# Gate_Strobe.net
KiCad netlist of a schematic drawn in Altium Designer
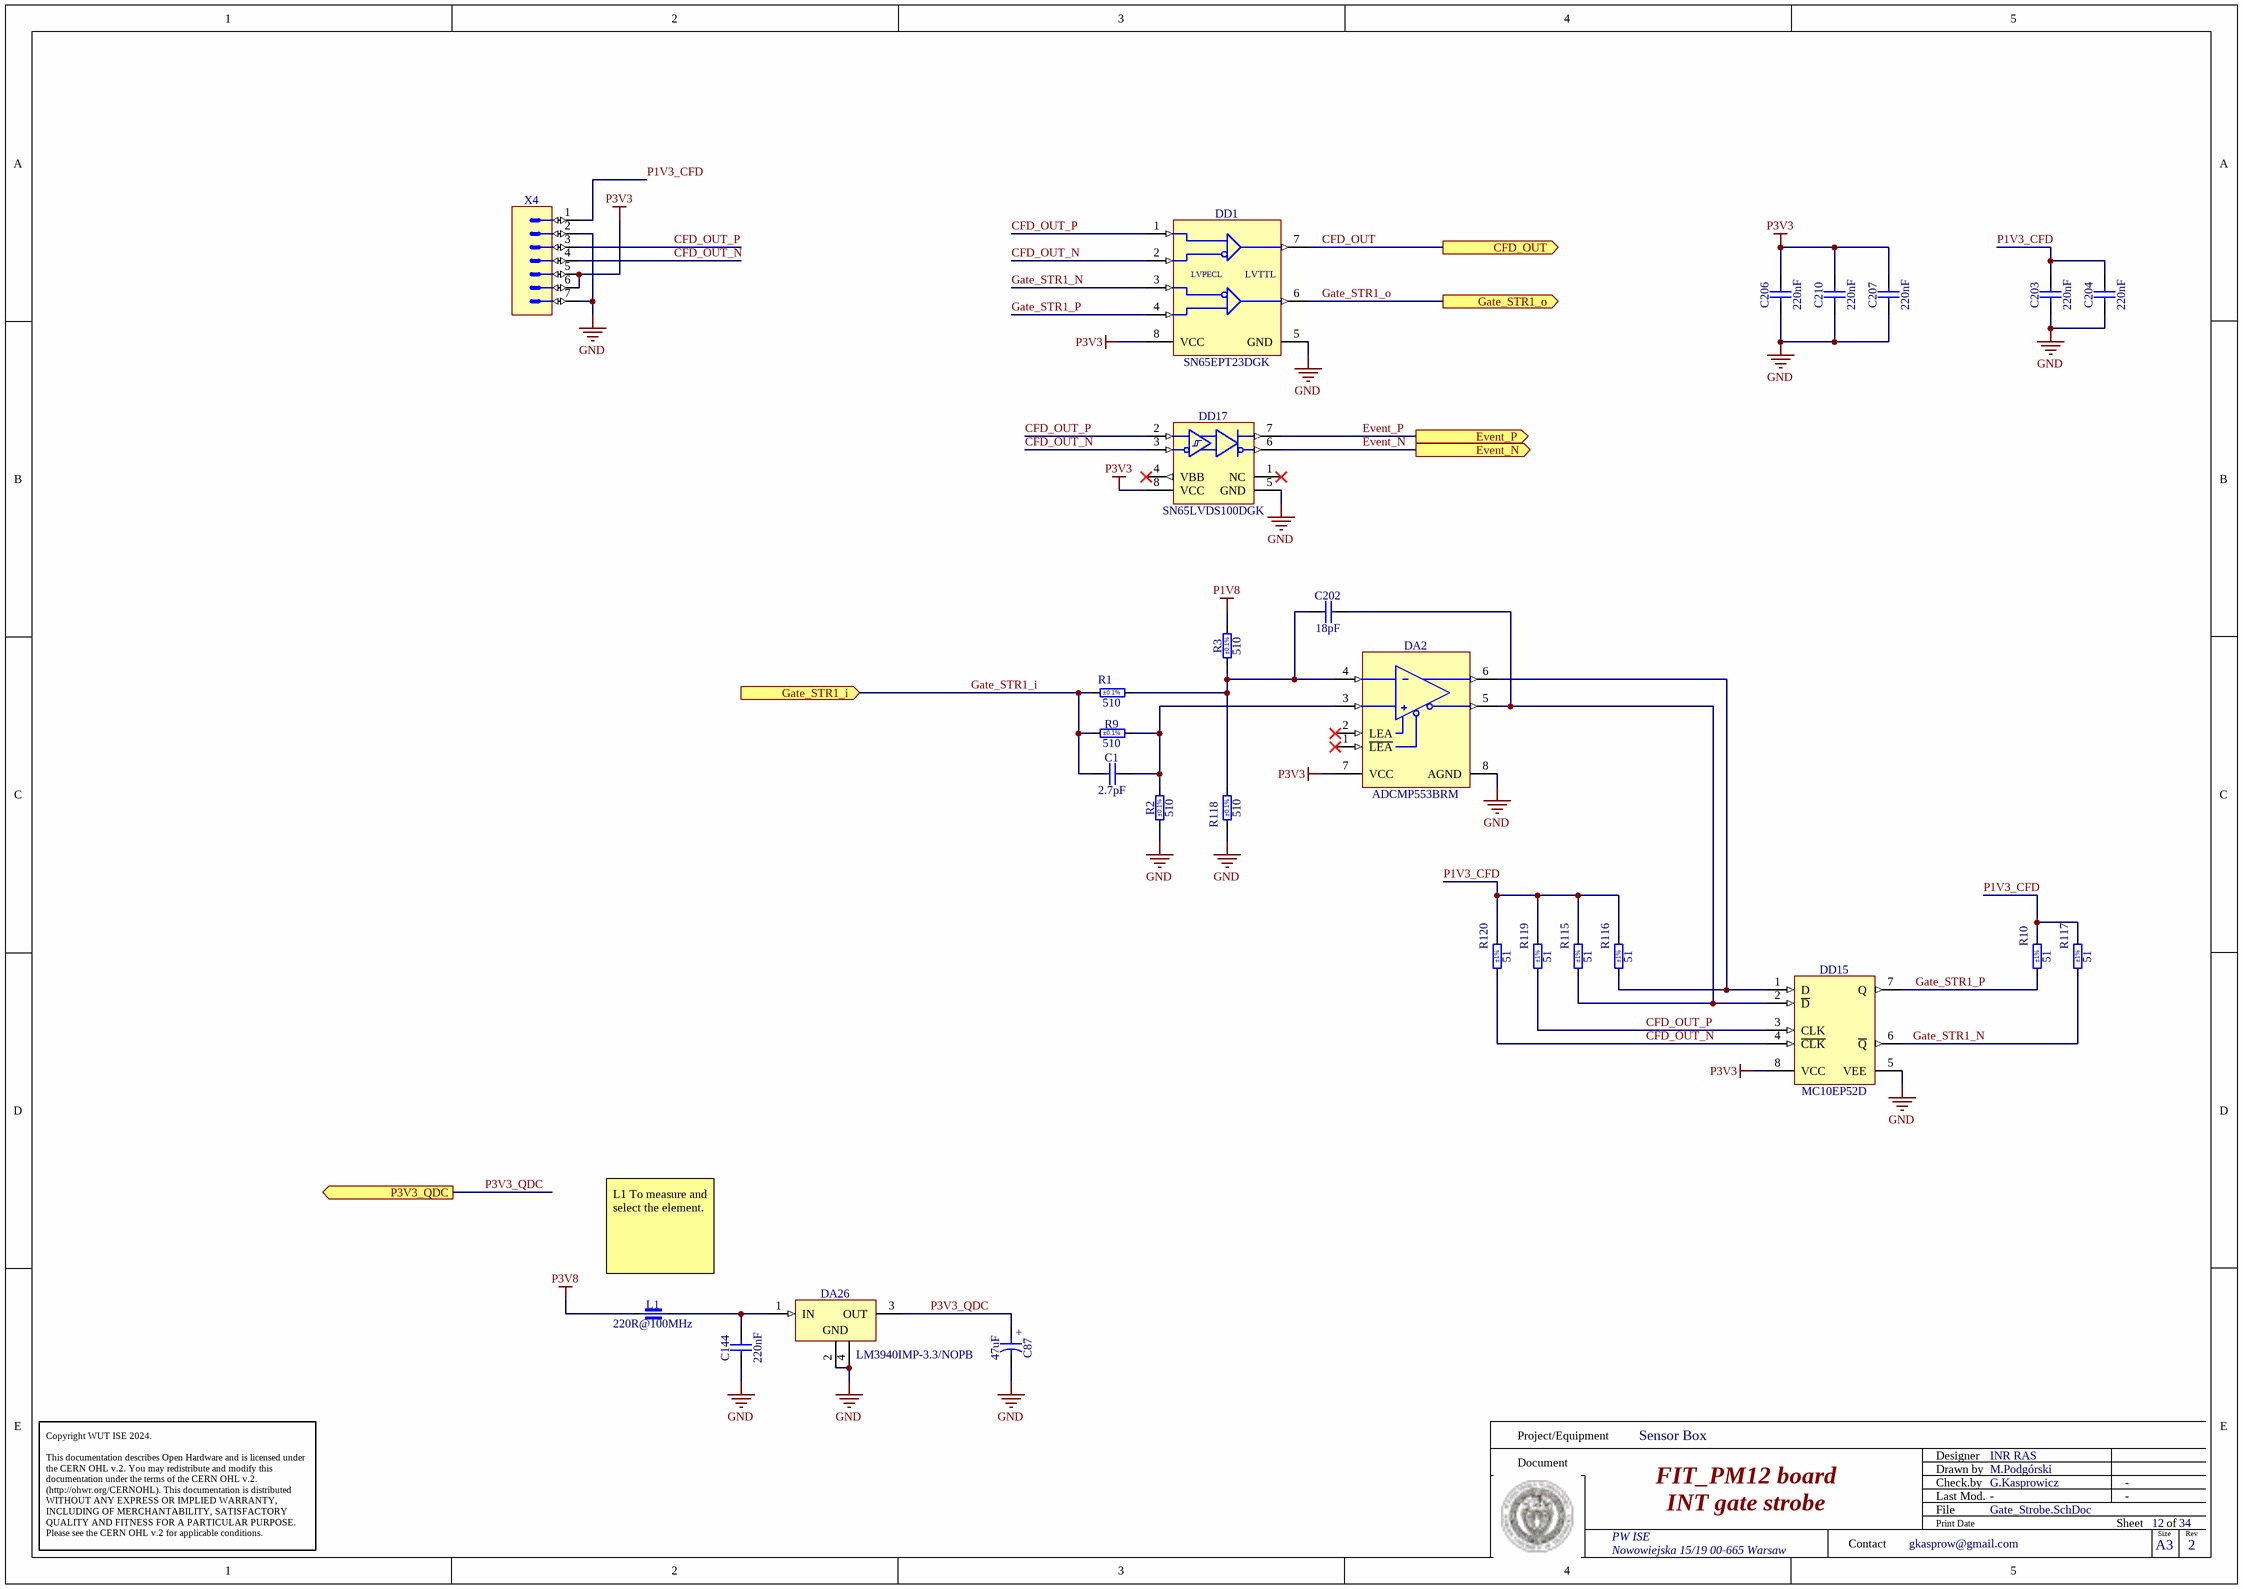
[diagram p0: Gate_Strobe.SchDoc]

(export (version "E")
  (design (tool "Eeschema 10.0.6"))
  (components
    (comp (ref "C1")
      (value "2.7pF")
      (footprint "CAPC2012X135N")
      (description "Non-polarised capacitor")
      (fields
        (field (name "PART NUMBER") "CC0805_2.7PF_250V_0.05PF_NP0")
        (field (name "VOLTAGE") "50V")
        (field (name "AUTHOR") "CERN DEM HF")
      )
      (libsource (lib "Capacitors") (part "Capacitor - non polarized"))
    )
    (comp (ref "C87")
      (value "47uF")
      (footprint "CAPAE530X610N")
      (description "Polarised capacitor")
      (fields
        (field (name "PART NUMBER") "CAE530-610_47UF_16V_20%")
        (field (name "VOLTAGE") "16V")
        (field (name "AUTHOR") "CERN DEM HF")
      )
      (libsource (lib "Capacitors") (part "Capacitor - polarized"))
    )
    (comp (ref "C144")
      (value "220nF")
      (footprint "CAPC2012X135N")
      (description "Non-polarised capacitor")
      (fields
        (field (name "PART NUMBER") "CC0805_220NF_50V_10%_X7R")
        (field (name "VOLTAGE") "50V")
        (field (name "AUTHOR") "CERN DEM JLC")
      )
      (libsource (lib "Capacitors") (part "Capacitor - non polarized"))
    )
    (comp (ref "C202")
      (value "18pF")
      (footprint "CAPC2012X88N")
      (description "Non-polarised capacitor")
      (fields
        (field (name "PART NUMBER") "CC0805_18PF_50V_1%_C0G")
        (field (name "VOLTAGE") "50V")
        (field (name "AUTHOR") "CERN DEM JLC")
      )
      (libsource (lib "Capacitors") (part "Capacitor - non polarized"))
    )
    (comp (ref "C203")
      (value "220nF")
      (footprint "CAPC2012X135N")
      (description "Non-polarised capacitor")
      (fields
        (field (name "PART NUMBER") "CC0805_220NF_50V_10%_X7R")
        (field (name "VOLTAGE") "50V")
        (field (name "AUTHOR") "CERN DEM JLC")
      )
      (libsource (lib "Capacitors") (part "Capacitor - non polarized"))
    )
    (comp (ref "C204")
      (value "220nF")
      (footprint "CAPC2012X135N")
      (description "Non-polarised capacitor")
      (fields
        (field (name "PART NUMBER") "CC0805_220NF_50V_10%_X7R")
        (field (name "VOLTAGE") "50V")
        (field (name "AUTHOR") "CERN DEM JLC")
      )
      (libsource (lib "Capacitors") (part "Capacitor - non polarized"))
    )
    (comp (ref "C206")
      (value "220nF")
      (footprint "CAPC2012X135N")
      (description "Non-polarised capacitor")
      (fields
        (field (name "PART NUMBER") "CC0805_220NF_50V_10%_X7R")
        (field (name "VOLTAGE") "50V")
        (field (name "AUTHOR") "CERN DEM JLC")
      )
      (libsource (lib "Capacitors") (part "Capacitor - non polarized"))
    )
    (comp (ref "C207")
      (value "220nF")
      (footprint "CAPC2012X135N")
      (description "Non-polarised capacitor")
      (fields
        (field (name "PART NUMBER") "CC0805_220NF_50V_10%_X7R")
        (field (name "VOLTAGE") "50V")
        (field (name "AUTHOR") "CERN DEM JLC")
      )
      (libsource (lib "Capacitors") (part "Capacitor - non polarized"))
    )
    (comp (ref "C210")
      (value "220nF")
      (footprint "CAPC2012X135N")
      (description "Non-polarised capacitor")
      (fields
        (field (name "PART NUMBER") "CC0805_220NF_50V_10%_X7R")
        (field (name "VOLTAGE") "50V")
        (field (name "AUTHOR") "CERN DEM JLC")
      )
      (libsource (lib "Capacitors") (part "Capacitor - non polarized"))
    )
    (comp (ref "DA2")
      (value "ADCMP553BRM")
      (footprint "SOP65P490X110-8N")
      (description "Single-Supply, High Speed PECL/LVPECL Comparators")
      (fields (field (name "MANUFACTURER") "ANALOG DEVICES") (field (name "AUTHOR") "CERN DEM HF"))
      (libsource (lib "ICs And Semiconductors") (part "ADCMP553BRM"))
    )
    (comp (ref "DA26")
      (value "LM3940IMP-3.3/NOPB")
      (footprint "SOT230P700X180-4N")
      (description "3-Terminal Regulator 1=IN 2=GND 3=OUT 4=GND")
      (fields
        (field (name "MANUFACTURER") "TEXAS INSTRUMENTS")
        (field (name "MANUFACTURER PART NUMBER") "LM3940IMP-3.3")
        (field (name "AUTHOR") "CERN DEM JLC")
      )
      (libsource (lib "ICs And Semiconductors") (part "REG3+1 1IN-2GND-3OUT+4GND"))
    )
    (comp (ref "DD1")
      (value "SN65EPT23DGK")
      (footprint "SOP65P490X110-8N")
      (description "5V PECL to TTL Translator")
      (fields (field (name "MANUFACTURER") "TEXAS INSTRUMENTS") (field (name "AUTHOR") "CERN DEM HF"))
      (libsource (lib "ICs And Semiconductors") (part "SN65EPT23"))
    )
    (comp (ref "DD15")
      (value "MC10EP52D")
      (footprint "SOIC127P600X175-8N")
      (description "3.3V/5V ECL Differential Data and Clock D Flip-Flop")
      (fields (field (name "MANUFACTURER") "ON SEMICONDUCTOR") (field (name "AUTHOR") "CERN DEM HF"))
      (libsource (lib "ICs And Semiconductors") (part "100EP52"))
    )
    (comp (ref "DD17")
      (value "SN65LVDS100DGK")
      (footprint "SOP65P490X110-8N")
      (description "Differential LVDS Translator/Repeater")
      (fields (field (name "MANUFACTURER") "TEXAS INSTRUMENTS") (field (name "AUTHOR") "CERN DEM JLC"))
      (libsource (lib "ICs And Semiconductors") (part "SN65LVDS100"))
    )
    (comp (ref "L1")
      (value "220R@100MHz")
      (footprint "INDC2012X105N")
      (fields
        (field (name "PART NUMBER") "IND0805_TDK_MPZ2012S221A")
        (field (name "POWER") "3A")
        (field (name "TOLERANCE") "±25%")
        (field (name "AUTHOR") "CERN DEM HF")
      )
      (libsource (lib "Inductors & Transformers") (part "Ferrite Bead"))
    )
    (comp (ref "R1")
      (value "510")
      (footprint "RESC2012X60N")
      (description "Resistor - 0.1%")
      (fields
        (field (name "TOLERANCE") "±0.1%")
        (field (name "PART NUMBER") "R0805_510R_0.1%_0.125W_10PPM")
        (field (name "POWER") "0.125W")
        (field (name "AUTHOR") "CERN DEM HF")
      )
      (libsource (lib "Resistors") (part "Resistor - 0.1%"))
    )
    (comp (ref "R2")
      (value "510")
      (footprint "RESC2012X60N")
      (description "Resistor - 0.1%")
      (fields
        (field (name "TOLERANCE") "±0.1%")
        (field (name "PART NUMBER") "R0805_510R_0.1%_0.125W_10PPM")
        (field (name "POWER") "0.125W")
        (field (name "AUTHOR") "CERN DEM HF")
      )
      (libsource (lib "Resistors") (part "Resistor - 0.1%"))
    )
    (comp (ref "R3")
      (value "510")
      (footprint "RESC2012X60N")
      (description "Resistor - 0.1%")
      (fields
        (field (name "TOLERANCE") "±0.1%")
        (field (name "PART NUMBER") "R0805_510R_0.1%_0.125W_10PPM")
        (field (name "POWER") "0.125W")
        (field (name "AUTHOR") "CERN DEM HF")
      )
      (libsource (lib "Resistors") (part "Resistor - 0.1%"))
    )
    (comp (ref "R9")
      (value "510")
      (footprint "RESC2012X60N")
      (description "Resistor - 0.1%")
      (fields
        (field (name "TOLERANCE") "±0.1%")
        (field (name "PART NUMBER") "R0805_510R_0.1%_0.125W_10PPM")
        (field (name "POWER") "0.125W")
        (field (name "AUTHOR") "CERN DEM HF")
      )
      (libsource (lib "Resistors") (part "Resistor - 0.1%"))
    )
    (comp (ref "R10")
      (value "51")
      (footprint "RESC2012X60N")
      (description "Resistor - 1%")
      (fields
        (field (name "TOLERANCE") "±1%")
        (field (name "PART NUMBER") "R0805_51R_1%_0.125W_100PPM")
        (field (name "POWER") "0.125W")
        (field (name "AUTHOR") "CERN DEM JLC")
      )
      (libsource (lib "Resistors") (part "Resistor - 1%"))
    )
    (comp (ref "R115")
      (value "51")
      (footprint "RESC2012X60N")
      (description "Resistor - 1%")
      (fields
        (field (name "TOLERANCE") "±1%")
        (field (name "PART NUMBER") "R0805_51R_1%_0.125W_100PPM")
        (field (name "POWER") "0.125W")
        (field (name "AUTHOR") "CERN DEM JLC")
      )
      (libsource (lib "Resistors") (part "Resistor - 1%"))
    )
    (comp (ref "R116")
      (value "51")
      (footprint "RESC2012X60N")
      (description "Resistor - 1%")
      (fields
        (field (name "TOLERANCE") "±1%")
        (field (name "PART NUMBER") "R0805_51R_1%_0.125W_100PPM")
        (field (name "POWER") "0.125W")
        (field (name "AUTHOR") "CERN DEM JLC")
      )
      (libsource (lib "Resistors") (part "Resistor - 1%"))
    )
    (comp (ref "R117")
      (value "51")
      (footprint "RESC2012X60N")
      (description "Resistor - 1%")
      (fields
        (field (name "TOLERANCE") "±1%")
        (field (name "PART NUMBER") "R0805_51R_1%_0.125W_100PPM")
        (field (name "POWER") "0.125W")
        (field (name "AUTHOR") "CERN DEM JLC")
      )
      (libsource (lib "Resistors") (part "Resistor - 1%"))
    )
    (comp (ref "R118")
      (value "510")
      (footprint "RESC2012X60N")
      (description "Resistor - 0.1%")
      (fields
        (field (name "TOLERANCE") "±0.1%")
        (field (name "PART NUMBER") "R0805_510R_0.1%_0.125W_10PPM")
        (field (name "POWER") "0.125W")
        (field (name "AUTHOR") "CERN DEM HF")
      )
      (libsource (lib "Resistors") (part "Resistor - 0.1%"))
    )
    (comp (ref "R119")
      (value "51")
      (footprint "RESC2012X60N")
      (description "Resistor - 1%")
      (fields
        (field (name "TOLERANCE") "±1%")
        (field (name "PART NUMBER") "R0805_51R_1%_0.125W_100PPM")
        (field (name "POWER") "0.125W")
        (field (name "AUTHOR") "CERN DEM JLC")
      )
      (libsource (lib "Resistors") (part "Resistor - 1%"))
    )
    (comp (ref "R120")
      (value "51")
      (footprint "RESC2012X60N")
      (description "Resistor - 1%")
      (fields
        (field (name "TOLERANCE") "±1%")
        (field (name "PART NUMBER") "R0805_51R_1%_0.125W_100PPM")
        (field (name "POWER") "0.125W")
        (field (name "AUTHOR") "CERN DEM JLC")
      )
      (libsource (lib "Resistors") (part "Resistor - 1%"))
    )
    (comp (ref "X4")
      (value "Header 7")
      (footprint "SAMTEC_DW-07-09-L-S-470")
      (description "Connector 7 Male")
      (fields
        (field (name "PART NUMBER") "SAMTEC_DW-07-09-L-S-470")
        (field (name "MANUFACTURER") "SAMTEC")
        (field (name "AUTHOR") "CERN DEM HF")
      )
      (libsource (lib "Connectors") (part "Connector 7 Male"))
    )
  )
  (nets
    (net (code "1") (name "/CFD_OUT") (class "Default")
      (node (ref "DD1") (pin "7") (pinfunction "Q0_7") (pintype "output"))
    )
    (net (code "2") (name "/CFD_OUT_N") (class "Default")
      (node (ref "DD1") (pin "2") (pinfunction "~{D0}_2") (pintype "input"))
      (node (ref "DD15") (pin "4") (pinfunction "~{CLK}_4") (pintype "input"))
      (node (ref "DD17") (pin "3") (pinfunction "B_3") (pintype "input"))
      (node (ref "R120") (pin "1") (pinfunction "1_1") (pintype "passive"))
      (node (ref "X4") (pin "4") (pinfunction "4_4") (pintype "bidirectional"))
    )
    (net (code "3") (name "/CFD_OUT_P") (class "Default")
      (node (ref "DD1") (pin "1") (pinfunction "D0_1") (pintype "input"))
      (node (ref "DD15") (pin "3") (pinfunction "CLK_3") (pintype "input"))
      (node (ref "DD17") (pin "2") (pinfunction "A_2") (pintype "input"))
      (node (ref "R119") (pin "1") (pinfunction "1_1") (pintype "passive"))
      (node (ref "X4") (pin "3") (pinfunction "3_3") (pintype "bidirectional"))
    )
    (net (code "4") (name "/Event_N") (class "Default")
      (node (ref "DD17") (pin "6") (pinfunction "Z_6") (pintype "output"))
    )
    (net (code "5") (name "/Event_P") (class "Default")
      (node (ref "DD17") (pin "7") (pinfunction "Y_7") (pintype "output"))
    )
    (net (code "6") (name "/Gate_STR1_N") (class "Default")
      (node (ref "DD1") (pin "3") (pinfunction "~{D1}_3") (pintype "input"))
      (node (ref "DD15") (pin "6") (pinfunction "~{Q}_6") (pintype "output"))
      (node (ref "R117") (pin "1") (pinfunction "1_1") (pintype "passive"))
    )
    (net (code "7") (name "/Gate_STR1_P") (class "Default")
      (node (ref "DD1") (pin "4") (pinfunction "D1_4") (pintype "input"))
      (node (ref "DD15") (pin "7") (pinfunction "Q_7") (pintype "output"))
      (node (ref "R10") (pin "1") (pinfunction "1_1") (pintype "passive"))
    )
    (net (code "8") (name "/Gate_STR1_i") (class "Default")
      (node (ref "C1") (pin "1") (pinfunction "1_1") (pintype "passive"))
      (node (ref "R1") (pin "1") (pinfunction "1_1") (pintype "passive"))
      (node (ref "R9") (pin "1") (pinfunction "1_1") (pintype "passive"))
    )
    (net (code "9") (name "/Gate_STR1_o") (class "Default")
      (node (ref "DD1") (pin "6") (pinfunction "Q1_6") (pintype "output"))
    )
    (net (code "10") (name "/P1V3_CFD") (class "Default")
      (node (ref "C203") (pin "2") (pinfunction "2_2") (pintype "passive"))
      (node (ref "C204") (pin "2") (pinfunction "2_2") (pintype "passive"))
      (node (ref "R10") (pin "2") (pinfunction "2_2") (pintype "passive"))
      (node (ref "R115") (pin "2") (pinfunction "2_2") (pintype "passive"))
      (node (ref "R116") (pin "2") (pinfunction "2_2") (pintype "passive"))
      (node (ref "R117") (pin "2") (pinfunction "2_2") (pintype "passive"))
      (node (ref "R119") (pin "2") (pinfunction "2_2") (pintype "passive"))
      (node (ref "R120") (pin "2") (pinfunction "2_2") (pintype "passive"))
      (node (ref "X4") (pin "1") (pinfunction "1_1") (pintype "bidirectional"))
    )
    (net (code "11") (name "/P3V3_QDC") (class "Default")
      (node (ref "C87") (pin "1") (pinfunction "1_1") (pintype "passive"))
      (node (ref "DA26") (pin "3") (pinfunction "OUT_3") (pintype "power_in"))
    )
    (net (code "12") (name "GND") (class "Default")
      (node (ref "C144") (pin "1") (pinfunction "1_1") (pintype "passive"))
      (node (ref "C203") (pin "1") (pinfunction "1_1") (pintype "passive"))
      (node (ref "C204") (pin "1") (pinfunction "1_1") (pintype "passive"))
      (node (ref "C206") (pin "1") (pinfunction "1_1") (pintype "passive"))
      (node (ref "C207") (pin "1") (pinfunction "1_1") (pintype "passive"))
      (node (ref "C210") (pin "1") (pinfunction "1_1") (pintype "passive"))
      (node (ref "C87") (pin "2") (pinfunction "2_2") (pintype "passive"))
      (node (ref "DA2") (pin "8") (pinfunction "AGND_8") (pintype "power_in"))
      (node (ref "DA26") (pin "2") (pinfunction "GND_2") (pintype "power_in"))
      (node (ref "DA26") (pin "4") (pinfunction "GND_4") (pintype "power_in"))
      (node (ref "DD1") (pin "5") (pinfunction "GND_5") (pintype "power_in"))
      (node (ref "DD15") (pin "5") (pinfunction "VEE_5") (pintype "power_in"))
      (node (ref "DD17") (pin "5") (pinfunction "GND_5") (pintype "power_in"))
      (node (ref "R118") (pin "1") (pinfunction "1_1") (pintype "passive"))
      (node (ref "R2") (pin "1") (pinfunction "1_1") (pintype "passive"))
      (node (ref "X4") (pin "2") (pinfunction "2_2") (pintype "bidirectional"))
      (node (ref "X4") (pin "7") (pinfunction "7_7") (pintype "bidirectional"))
    )
    (net (code "13") (name "Net-(DA2-+INA)") (class "Default")
      (node (ref "C1") (pin "2") (pinfunction "2_2") (pintype "passive"))
      (node (ref "DA2") (pin "3") (pinfunction "+INA_3") (pintype "input"))
      (node (ref "R2") (pin "2") (pinfunction "2_2") (pintype "passive"))
      (node (ref "R9") (pin "2") (pinfunction "2_2") (pintype "passive"))
    )
    (net (code "14") (name "Net-(DA2--INA)") (class "Default")
      (node (ref "C202") (pin "1") (pinfunction "1_1") (pintype "passive"))
      (node (ref "DA2") (pin "4") (pinfunction "-INA_4") (pintype "input"))
      (node (ref "R1") (pin "2") (pinfunction "2_2") (pintype "passive"))
      (node (ref "R118") (pin "2") (pinfunction "2_2") (pintype "passive"))
      (node (ref "R3") (pin "1") (pinfunction "1_1") (pintype "passive"))
    )
    (net (code "15") (name "Net-(DA2-QA)") (class "Default")
      (node (ref "DA2") (pin "6") (pinfunction "QA_6") (pintype "output"))
      (node (ref "DD15") (pin "1") (pinfunction "D_1") (pintype "input"))
      (node (ref "R116") (pin "1") (pinfunction "1_1") (pintype "passive"))
    )
    (net (code "16") (name "Net-(DA2-~{QA})") (class "Default")
      (node (ref "C202") (pin "2") (pinfunction "2_2") (pintype "passive"))
      (node (ref "DA2") (pin "5") (pinfunction "~{QA}_5") (pintype "output"))
      (node (ref "DD15") (pin "2") (pinfunction "~{D}_2") (pintype "input"))
      (node (ref "R115") (pin "1") (pinfunction "1_1") (pintype "passive"))
    )
    (net (code "17") (name "Net-(DA26-IN)") (class "Default")
      (node (ref "C144") (pin "2") (pinfunction "2_2") (pintype "passive"))
      (node (ref "DA26") (pin "1") (pinfunction "IN_1") (pintype "input"))
      (node (ref "L1") (pin "2") (pinfunction "2_2") (pintype "passive"))
    )
    (net (code "18") (name "P1V8") (class "Default")
      (node (ref "R3") (pin "2") (pinfunction "2_2") (pintype "passive"))
    )
    (net (code "19") (name "P3V3") (class "Default")
      (node (ref "C206") (pin "2") (pinfunction "2_2") (pintype "passive"))
      (node (ref "C207") (pin "2") (pinfunction "2_2") (pintype "passive"))
      (node (ref "C210") (pin "2") (pinfunction "2_2") (pintype "passive"))
      (node (ref "DA2") (pin "7") (pinfunction "VCC_7") (pintype "power_in"))
      (node (ref "DD1") (pin "8") (pinfunction "VCC_8") (pintype "power_in"))
      (node (ref "DD15") (pin "8") (pinfunction "VCC_8") (pintype "power_in"))
      (node (ref "DD17") (pin "8") (pinfunction "VCC_8") (pintype "power_in"))
      (node (ref "X4") (pin "5") (pinfunction "5_5") (pintype "bidirectional"))
      (node (ref "X4") (pin "6") (pinfunction "6_6") (pintype "bidirectional"))
    )
    (net (code "20") (name "P3V8") (class "Default")
      (node (ref "L1") (pin "1") (pinfunction "1_1") (pintype "passive"))
    )
    (net (code "21") (name "unconnected-(DA2-LEA-Pad2)") (class "Default")
      (node (ref "DA2") (pin "2") (pinfunction "LEA_2") (pintype "input+no_connect"))
    )
    (net (code "22") (name "unconnected-(DA2-~{LEA}-Pad1)") (class "Default")
      (node (ref "DA2") (pin "1") (pinfunction "~{LEA}_1") (pintype "input+no_connect"))
    )
    (net (code "23") (name "unconnected-(DD17-NC-Pad1)") (class "Default")
      (node (ref "DD17") (pin "1") (pinfunction "NC_1") (pintype "passive+no_connect"))
    )
    (net (code "24") (name "unconnected-(DD17-VBB-Pad4)") (class "Default")
      (node (ref "DD17") (pin "4") (pinfunction "VBB_4") (pintype "output+no_connect"))
    )
  )
)
